# Sheet1.net
KiCad netlist of a schematic drawn in Altium Designer
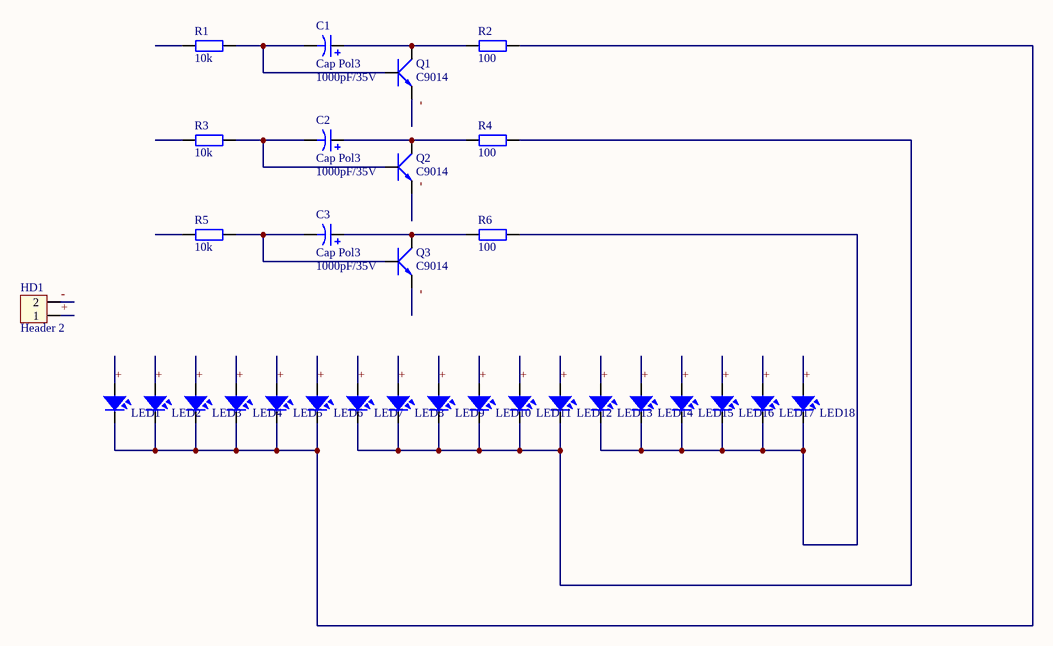
[diagram p0: Sheet1.SchDoc]

(export (version "E")
  (design (tool "Eeschema 10.0.6"))
  (components
    (comp (ref "C1")
      (value "Cap Pol3")
      (footprint "CP2/5")
      (description "Polarized Capacitor (Surface Mount)")
      (fields (field (name "ALTIUM_VALUE") "1000pF/35V") (field (name "PUBLISHER") "Altium Limited"))
      (libsource (lib "syhaunguyen") (part "Cap Pol3_1"))
    )
    (comp (ref "C2")
      (value "Cap Pol3")
      (footprint "CP2/5")
      (description "Polarized Capacitor (Surface Mount)")
      (fields (field (name "ALTIUM_VALUE") "1000pF/35V") (field (name "PUBLISHER") "Altium Limited"))
      (libsource (lib "syhaunguyen") (part "Cap Pol3_1"))
    )
    (comp (ref "C3")
      (value "Cap Pol3")
      (footprint "CP2/5")
      (description "Polarized Capacitor (Surface Mount)")
      (fields (field (name "ALTIUM_VALUE") "1000pF/35V") (field (name "PUBLISHER") "Altium Limited"))
      (libsource (lib "syhaunguyen") (part "Cap Pol3_1"))
    )
    (comp (ref "HD1")
      (value "Header 2")
      (footprint "HED2B")
      (description "Header 2 (Green)")
      (libsource (lib "syhaunguyen") (part "Hed2"))
    )
    (comp (ref "LED1")
      (value "LED")
      (footprint "LED-5-RED")
      (description "LED Single colour Green and Red")
      (libsource (lib "syhaunguyen") (part "LED"))
    )
    (comp (ref "LED2")
      (value "LED")
      (footprint "LED-5-RED")
      (description "LED Single colour Green and Red")
      (libsource (lib "syhaunguyen") (part "LED"))
    )
    (comp (ref "LED3")
      (value "LED")
      (footprint "LED-5-RED")
      (description "LED Single colour Green and Red")
      (libsource (lib "syhaunguyen") (part "LED"))
    )
    (comp (ref "LED4")
      (value "LED")
      (footprint "LED-5-RED")
      (description "LED Single colour Green and Red")
      (libsource (lib "syhaunguyen") (part "LED"))
    )
    (comp (ref "LED5")
      (value "LED")
      (footprint "LED-5-RED")
      (description "LED Single colour Green and Red")
      (libsource (lib "syhaunguyen") (part "LED"))
    )
    (comp (ref "LED6")
      (value "LED")
      (footprint "LED-5-RED")
      (description "LED Single colour Green and Red")
      (libsource (lib "syhaunguyen") (part "LED"))
    )
    (comp (ref "LED7")
      (value "LED")
      (footprint "LED-5-RED")
      (description "LED Single colour Green and Red")
      (libsource (lib "syhaunguyen") (part "LED"))
    )
    (comp (ref "LED8")
      (value "LED")
      (footprint "LED-5-RED")
      (description "LED Single colour Green and Red")
      (libsource (lib "syhaunguyen") (part "LED"))
    )
    (comp (ref "LED9")
      (value "LED")
      (footprint "LED-5-RED")
      (description "LED Single colour Green and Red")
      (libsource (lib "syhaunguyen") (part "LED"))
    )
    (comp (ref "LED10")
      (value "LED")
      (footprint "LED-5-RED")
      (description "LED Single colour Green and Red")
      (libsource (lib "syhaunguyen") (part "LED"))
    )
    (comp (ref "LED11")
      (value "LED")
      (footprint "LED-5-RED")
      (description "LED Single colour Green and Red")
      (libsource (lib "syhaunguyen") (part "LED"))
    )
    (comp (ref "LED12")
      (value "LED")
      (footprint "LED-5-RED")
      (description "LED Single colour Green and Red")
      (libsource (lib "syhaunguyen") (part "LED"))
    )
    (comp (ref "LED13")
      (value "LED")
      (footprint "LED-5-RED")
      (description "LED Single colour Green and Red")
      (libsource (lib "syhaunguyen") (part "LED"))
    )
    (comp (ref "LED14")
      (value "LED")
      (footprint "LED-5-RED")
      (description "LED Single colour Green and Red")
      (libsource (lib "syhaunguyen") (part "LED"))
    )
    (comp (ref "LED15")
      (value "LED")
      (footprint "LED-5-RED")
      (description "LED Single colour Green and Red")
      (libsource (lib "syhaunguyen") (part "LED"))
    )
    (comp (ref "LED16")
      (value "LED")
      (footprint "LED-5-RED")
      (description "LED Single colour Green and Red")
      (libsource (lib "syhaunguyen") (part "LED"))
    )
    (comp (ref "LED17")
      (value "LED")
      (footprint "LED-5-RED")
      (description "LED Single colour Green and Red")
      (libsource (lib "syhaunguyen") (part "LED"))
    )
    (comp (ref "LED18")
      (value "LED")
      (footprint "LED-5-RED")
      (description "LED Single colour Green and Red")
      (libsource (lib "syhaunguyen") (part "LED"))
    )
    (comp (ref "Q1")
      (value "C9014")
      (footprint "QTO-92")
      (description "PNP 600mW, EBC")
      (libsource (lib "syhaunguyen") (part "C9014"))
    )
    (comp (ref "Q2")
      (value "C9014")
      (footprint "QTO-92")
      (description "PNP 600mW, EBC")
      (libsource (lib "syhaunguyen") (part "C9014"))
    )
    (comp (ref "Q3")
      (value "C9014")
      (footprint "QTO-92")
      (description "PNP 600mW, EBC")
      (libsource (lib "syhaunguyen") (part "C9014"))
    )
    (comp (ref "R1")
      (value "10k")
      (footprint "R1/4W")
      (description "Resistor 1/4W")
      (libsource (lib "syhaunguyen") (part "R1/4W"))
    )
    (comp (ref "R2")
      (value "100")
      (footprint "R1/4W")
      (description "Resistor 1/4W")
      (libsource (lib "syhaunguyen") (part "R1/4W"))
    )
    (comp (ref "R3")
      (value "10k")
      (footprint "R1/4W")
      (description "Resistor 1/4W")
      (libsource (lib "syhaunguyen") (part "R1/4W"))
    )
    (comp (ref "R4")
      (value "100")
      (footprint "R1/4W")
      (description "Resistor 1/4W")
      (libsource (lib "syhaunguyen") (part "R1/4W"))
    )
    (comp (ref "R5")
      (value "10k")
      (footprint "R1/4W")
      (description "Resistor 1/4W")
      (libsource (lib "syhaunguyen") (part "R1/4W"))
    )
    (comp (ref "R6")
      (value "100")
      (footprint "R1/4W")
      (description "Resistor 1/4W")
      (libsource (lib "syhaunguyen") (part "R1/4W"))
    )
  )
  (nets
    (net (code "1") (name "/+") (class "Default")
      (node (ref "HD1") (pin "1") (pinfunction "1_1") (pintype "passive"))
      (node (ref "LED1") (pin "1") (pinfunction "1_1") (pintype "passive"))
      (node (ref "LED10") (pin "1") (pinfunction "1_1") (pintype "passive"))
      (node (ref "LED11") (pin "1") (pinfunction "1_1") (pintype "passive"))
      (node (ref "LED12") (pin "1") (pinfunction "1_1") (pintype "passive"))
      (node (ref "LED13") (pin "1") (pinfunction "1_1") (pintype "passive"))
      (node (ref "LED14") (pin "1") (pinfunction "1_1") (pintype "passive"))
      (node (ref "LED15") (pin "1") (pinfunction "1_1") (pintype "passive"))
      (node (ref "LED16") (pin "1") (pinfunction "1_1") (pintype "passive"))
      (node (ref "LED17") (pin "1") (pinfunction "1_1") (pintype "passive"))
      (node (ref "LED18") (pin "1") (pinfunction "1_1") (pintype "passive"))
      (node (ref "LED2") (pin "1") (pinfunction "1_1") (pintype "passive"))
      (node (ref "LED3") (pin "1") (pinfunction "1_1") (pintype "passive"))
      (node (ref "LED4") (pin "1") (pinfunction "1_1") (pintype "passive"))
      (node (ref "LED5") (pin "1") (pinfunction "1_1") (pintype "passive"))
      (node (ref "LED6") (pin "1") (pinfunction "1_1") (pintype "passive"))
      (node (ref "LED7") (pin "1") (pinfunction "1_1") (pintype "passive"))
      (node (ref "LED8") (pin "1") (pinfunction "1_1") (pintype "passive"))
      (node (ref "LED9") (pin "1") (pinfunction "1_1") (pintype "passive"))
    )
    (net (code "2") (name "/-") (class "Default")
      (node (ref "HD1") (pin "2") (pinfunction "2_2") (pintype "passive"))
      (node (ref "Q1") (pin "1") (pinfunction "E_1") (pintype "passive"))
      (node (ref "Q3") (pin "1") (pinfunction "E_1") (pintype "passive"))
    )
    (net (code "3") (name "Net-(LED1-Pad2)") (class "Default")
      (node (ref "LED1") (pin "2") (pinfunction "2_2") (pintype "passive"))
      (node (ref "LED2") (pin "2") (pinfunction "2_2") (pintype "passive"))
      (node (ref "LED3") (pin "2") (pinfunction "2_2") (pintype "passive"))
      (node (ref "LED4") (pin "2") (pinfunction "2_2") (pintype "passive"))
      (node (ref "LED5") (pin "2") (pinfunction "2_2") (pintype "passive"))
      (node (ref "LED6") (pin "2") (pinfunction "2_2") (pintype "passive"))
      (node (ref "R2") (pin "1") (pinfunction "1_1") (pintype "passive"))
    )
    (net (code "4") (name "Net-(LED10-Pad2)") (class "Default")
      (node (ref "LED10") (pin "2") (pinfunction "2_2") (pintype "passive"))
      (node (ref "LED11") (pin "2") (pinfunction "2_2") (pintype "passive"))
      (node (ref "LED12") (pin "2") (pinfunction "2_2") (pintype "passive"))
      (node (ref "LED7") (pin "2") (pinfunction "2_2") (pintype "passive"))
      (node (ref "LED8") (pin "2") (pinfunction "2_2") (pintype "passive"))
      (node (ref "LED9") (pin "2") (pinfunction "2_2") (pintype "passive"))
      (node (ref "R4") (pin "1") (pinfunction "1_1") (pintype "passive"))
    )
    (net (code "5") (name "Net-(LED13-Pad2)") (class "Default")
      (node (ref "LED13") (pin "2") (pinfunction "2_2") (pintype "passive"))
      (node (ref "LED14") (pin "2") (pinfunction "2_2") (pintype "passive"))
      (node (ref "LED15") (pin "2") (pinfunction "2_2") (pintype "passive"))
      (node (ref "LED16") (pin "2") (pinfunction "2_2") (pintype "passive"))
      (node (ref "LED17") (pin "2") (pinfunction "2_2") (pintype "passive"))
      (node (ref "LED18") (pin "2") (pinfunction "2_2") (pintype "passive"))
      (node (ref "R6") (pin "1") (pinfunction "1_1") (pintype "passive"))
    )
    (net (code "6") (name "Net-(Q1-B)") (class "Default")
      (node (ref "C1") (pin "2") (pinfunction "2_2") (pintype "passive"))
      (node (ref "Q1") (pin "2") (pinfunction "B_2") (pintype "passive"))
      (node (ref "R1") (pin "1") (pinfunction "1_1") (pintype "passive"))
    )
    (net (code "7") (name "Net-(Q1-C)") (class "Default")
      (node (ref "C1") (pin "1") (pinfunction "1_1") (pintype "passive"))
      (node (ref "Q1") (pin "3") (pinfunction "C_3") (pintype "passive"))
      (node (ref "R2") (pin "2") (pinfunction "2_2") (pintype "passive"))
    )
    (net (code "8") (name "Net-(Q2-B)") (class "Default")
      (node (ref "C2") (pin "2") (pinfunction "2_2") (pintype "passive"))
      (node (ref "Q2") (pin "2") (pinfunction "B_2") (pintype "passive"))
      (node (ref "R3") (pin "1") (pinfunction "1_1") (pintype "passive"))
    )
    (net (code "9") (name "Net-(Q2-C)") (class "Default")
      (node (ref "C2") (pin "1") (pinfunction "1_1") (pintype "passive"))
      (node (ref "Q2") (pin "3") (pinfunction "C_3") (pintype "passive"))
      (node (ref "R4") (pin "2") (pinfunction "2_2") (pintype "passive"))
    )
    (net (code "10") (name "Net-(Q3-B)") (class "Default")
      (node (ref "C3") (pin "2") (pinfunction "2_2") (pintype "passive"))
      (node (ref "Q3") (pin "2") (pinfunction "B_2") (pintype "passive"))
      (node (ref "R5") (pin "1") (pinfunction "1_1") (pintype "passive"))
    )
    (net (code "11") (name "Net-(Q3-C)") (class "Default")
      (node (ref "C3") (pin "1") (pinfunction "1_1") (pintype "passive"))
      (node (ref "Q3") (pin "3") (pinfunction "C_3") (pintype "passive"))
      (node (ref "R6") (pin "2") (pinfunction "2_2") (pintype "passive"))
    )
    (net (code "12") (name "unconnected-(Q2-E-Pad1)") (class "Default")
      (node (ref "Q2") (pin "1") (pinfunction "E_1") (pintype "passive"))
    )
    (net (code "13") (name "unconnected-(R1-Pad2)") (class "Default")
      (node (ref "R1") (pin "2") (pinfunction "2_2") (pintype "passive"))
    )
    (net (code "14") (name "unconnected-(R3-Pad2)") (class "Default")
      (node (ref "R3") (pin "2") (pinfunction "2_2") (pintype "passive"))
    )
    (net (code "15") (name "unconnected-(R5-Pad2)") (class "Default")
      (node (ref "R5") (pin "2") (pinfunction "2_2") (pintype "passive"))
    )
  )
)
